# Video.net
KiCad netlist of a schematic drawn in Altium Designer
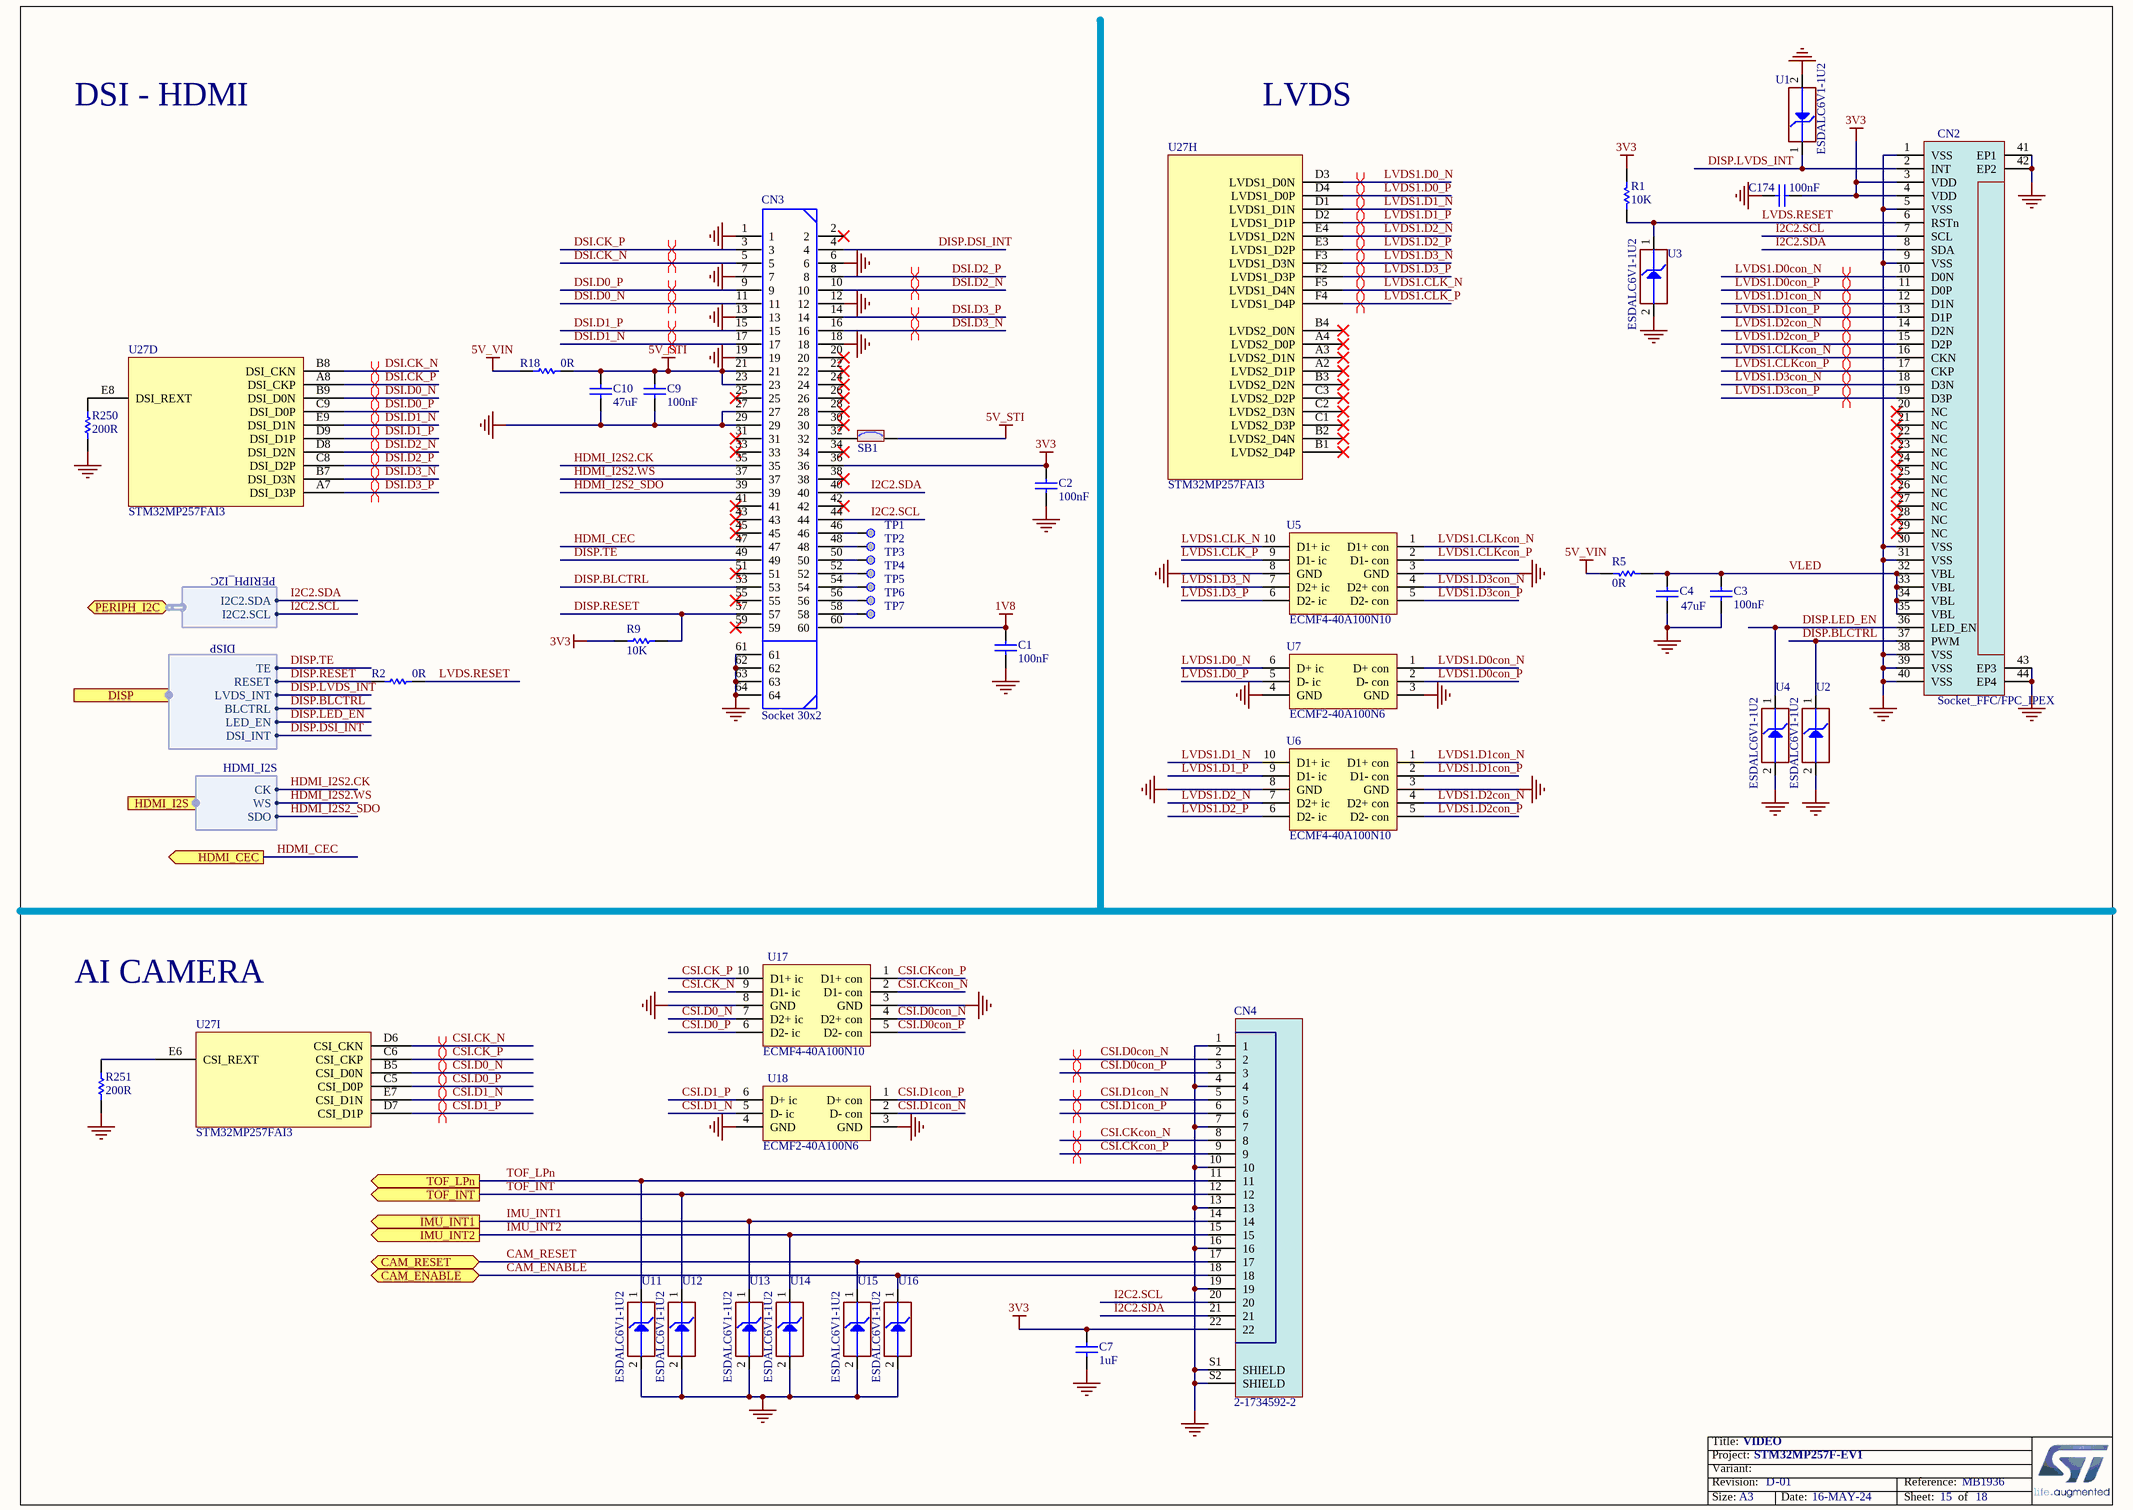
[diagram p0: Video.SchDoc]

(export (version "E")
  (design (tool "Eeschema 10.0.6"))
  (components
    (comp (ref "C1")
      (value "100nF")
      (footprint "MCD_PARTS:C0402")
      (description "Capacitor, MLCC, 100nF, 10V, X5R, +/-10%, 0402, T=0,5mm")
      (fields (field (name "INTERNAL_PART_NUMBER") "MCD-02352") (field (name "MANUFACTURER") "YAGEO"))
      (libsource (lib "MCD_PARTS_database") (part "Capacitor"))
    )
    (comp (ref "C2")
      (value "100nF")
      (footprint "MCD_PARTS:C0402")
      (description "Capacitor, MLCC, 100nF, 10V, X5R, +/-10%, 0402, T=0,5mm")
      (fields (field (name "INTERNAL_PART_NUMBER") "MCD-02352") (field (name "MANUFACTURER") "YAGEO"))
      (libsource (lib "MCD_PARTS_database") (part "Capacitor"))
    )
    (comp (ref "C3")
      (value "100nF")
      (footprint "MCD_PARTS:C0402")
      (description "Capacitor, MLCC, 100nF, 10V, X5R, +/-10%, 0402, T=0,5mm")
      (fields (field (name "INTERNAL_PART_NUMBER") "MCD-02352") (field (name "MANUFACTURER") "YAGEO"))
      (libsource (lib "MCD_PARTS_database") (part "Capacitor"))
    )
    (comp (ref "C4")
      (value "47uF")
      (footprint "MCD_PARTS:C0805")
      (description "Capacitor, MLCC, 47uF, 10V, X5R, +/-20%, 0805, T=1.25mm")
      (fields (field (name "INTERNAL_PART_NUMBER") "MCD-00204") (field (name "MANUFACTURER") "MURATA"))
      (libsource (lib "MCD_PARTS_database") (part "Capacitor"))
    )
    (comp (ref "C7")
      (value "1uF")
      (footprint "MCD_PARTS:C0402")
      (description "Capacitor, MLCC, 1uF, 25V, X5R, +/-10%, 0402, T=0,5mm")
      (fields
        (field (name "INTERNAL_PART_NUMBER") "MCD-00095")
        (field (name "MANUFACTURER_PART_NUMBER") "GRM155R61E105KA12")
      )
      (libsource (lib "MCD_PARTS_database") (part "Capacitor"))
    )
    (comp (ref "C9")
      (value "100nF")
      (footprint "MCD_PARTS:C0402")
      (description "Capacitor, MLCC, 100nF, 10V, X5R, +/-10%, 0402, T=0,5mm")
      (fields (field (name "INTERNAL_PART_NUMBER") "MCD-02352") (field (name "MANUFACTURER") "YAGEO"))
      (libsource (lib "MCD_PARTS_database") (part "Capacitor"))
    )
    (comp (ref "C10")
      (value "47uF")
      (footprint "MCD_PARTS:C0805")
      (description "Capacitor, MLCC, 47uF, 10V, X5R, +/-20%, 0805, T=1.25mm")
      (fields (field (name "INTERNAL_PART_NUMBER") "MCD-00204") (field (name "MANUFACTURER") "MURATA"))
      (libsource (lib "MCD_PARTS_database") (part "Capacitor"))
    )
    (comp (ref "C174")
      (value "100nF")
      (footprint "MCD_PARTS:C0402")
      (description "Capacitor, MLCC, 100nF, 10V, X5R, +/-10%, 0402, T=0,5mm")
      (fields (field (name "INTERNAL_PART_NUMBER") "MCD-02352") (field (name "MANUFACTURER") "YAGEO"))
      (libsource (lib "MCD_PARTS_database") (part "Capacitor"))
    )
    (comp (ref "CN2")
      (value "Socket_FFC/FPC_IPEX")
      (footprint "MCD_PARTS:CON_I-PEX_20455-040E-76")
      (description "Socket_FFC/FPC, 40pins, 0.5mm, RA, SMD, T=1mm")
      (fields (field (name "INTERNAL_PART_NUMBER") "MCD-03562") (field (name "MANUFACTURER") "I-PEX"))
      (libsource (lib "MCD_PARTS_database") (part "IPEX20455"))
    )
    (comp (ref "CN3")
      (value "Socket 30x2")
      (footprint "MCD_PARTS:CON_SAMTEC_QSH-030-01-F-D-A")
      (description "Socket, 30x2, 0.5mm, VR, SMD, T=3.05mm")
      (fields (field (name "INTERNAL_PART_NUMBER") "MCD-00137") (field (name "BMS_PART_NUMBER") "9183715"))
      (libsource (lib "MCD_PARTS_database") (part "Socket QSH-030-01-F-D-A"))
    )
    (comp (ref "CN4")
      (value "2-1734592-2")
      (footprint "MCD_PARTS:CON_TE-CONNECTIVITY_2-1734592-2_INV")
      (description "Socket_FFC/FPC, 22pins, 0.5mm, RA, SMD, T=2mm")
      (fields
        (field (name "INTERNAL_PART_NUMBER") "MCD-03600")
        (field (name "MANUFACTURER") "TE CONNECTIVITY")
      )
      (libsource (lib "MCD_PARTS_database") (part "2-1734592-2"))
    )
    (comp (ref "R1")
      (value "10K")
      (footprint "MCD_PARTS:R0402")
      (description "Resistor, 10K, 0402, +/-1%, 1/16W")
      (fields (field (name "INTERNAL_PART_NUMBER") "MCD-00053") (field (name "BMS_PART_NUMBER") "9131590"))
      (libsource (lib "MCD_PARTS_database") (part "Resistor"))
    )
    (comp (ref "R2")
      (value "0R")
      (footprint "MCD_PARTS:R0402")
      (description "Resistor, 0R, 0402, +/-5%, 1/16W")
      (fields (field (name "INTERNAL_PART_NUMBER") "MCD-00052") (field (name "MANUFACTURER") "YAGEO"))
      (libsource (lib "MCD_PARTS_database") (part "Resistor"))
    )
    (comp (ref "R5")
      (value "0R")
      (footprint "MCD_PARTS:R0805")
      (description "Resistor, 0R, 0805, +/-5%, 1/8W")
      (fields (field (name "INTERNAL_PART_NUMBER") "MCD-00179") (field (name "MANUFACTURER") "YAGEO"))
      (libsource (lib "MCD_PARTS_database") (part "Resistor"))
    )
    (comp (ref "R9")
      (value "10K")
      (footprint "MCD_PARTS:R0402")
      (description "Resistor, 10K, 0402, +/-1%, 1/16W")
      (fields (field (name "INTERNAL_PART_NUMBER") "MCD-00053") (field (name "BMS_PART_NUMBER") "9131590"))
      (libsource (lib "MCD_PARTS_database") (part "Resistor"))
    )
    (comp (ref "R18")
      (value "0R")
      (footprint "MCD_PARTS:R0402")
      (description "Resistor, 0R, 0402, +/-5%, 1/16W")
      (fields (field (name "INTERNAL_PART_NUMBER") "MCD-00052") (field (name "MANUFACTURER") "YAGEO"))
      (libsource (lib "MCD_PARTS_database") (part "Resistor"))
    )
    (comp (ref "R250")
      (value "200R")
      (footprint "MCD_PARTS:R0402")
      (description "Resistor, 200R, 0402, +/-1%, 1/16W")
      (fields
        (field (name "INTERNAL_PART_NUMBER") "MCD-00417")
        (field (name "MANUFACTURER_PART_NUMBER") "RC0402FR-07200RL")
      )
      (libsource (lib "MCD_PARTS_database") (part "Resistor"))
    )
    (comp (ref "R251")
      (value "200R")
      (footprint "MCD_PARTS:R0402")
      (description "Resistor, 200R, 0402, +/-1%, 1/16W")
      (fields
        (field (name "INTERNAL_PART_NUMBER") "MCD-00417")
        (field (name "MANUFACTURER_PART_NUMBER") "RC0402FR-07200RL")
      )
      (libsource (lib "MCD_PARTS_database") (part "Resistor"))
    )
    (comp (ref "SB1")
      (value "SB_ON")
      (footprint "MCD_PARTS:SOLDER-BRIDGE_R0603-0R")
      (description "Solder Bridge ON")
      (fields (field (name "INTERNAL_PART_NUMBER") "MCD-00071") (field (name "MANUFACTURER") "YAGEO"))
      (libsource (lib "MCD_PARTS_database") (part "SB_ON"))
    )
    (comp (ref "TP1")
      (value "Test Point")
      (footprint "MCD_PARTS:TP_SMD_1MM")
      (description "Test Point 1mm")
      (fields
        (field (name "INTERNAL_PART_NUMBER") "MCD-00074")
        (field (name "MANUFACTURER_PART_NUMBER") "n/a")
      )
      (libsource (lib "MCD_PARTS_database") (part "Test Point"))
    )
    (comp (ref "TP2")
      (value "Test Point")
      (footprint "MCD_PARTS:TP_SMD_1MM")
      (description "Test Point 1mm")
      (fields
        (field (name "INTERNAL_PART_NUMBER") "MCD-00074")
        (field (name "MANUFACTURER_PART_NUMBER") "n/a")
      )
      (libsource (lib "MCD_PARTS_database") (part "Test Point"))
    )
    (comp (ref "TP3")
      (value "Test Point")
      (footprint "MCD_PARTS:TP_SMD_1MM")
      (description "Test Point 1mm")
      (fields
        (field (name "INTERNAL_PART_NUMBER") "MCD-00074")
        (field (name "MANUFACTURER_PART_NUMBER") "n/a")
      )
      (libsource (lib "MCD_PARTS_database") (part "Test Point"))
    )
    (comp (ref "TP4")
      (value "Test Point")
      (footprint "MCD_PARTS:TP_SMD_1MM")
      (description "Test Point 1mm")
      (fields
        (field (name "INTERNAL_PART_NUMBER") "MCD-00074")
        (field (name "MANUFACTURER_PART_NUMBER") "n/a")
      )
      (libsource (lib "MCD_PARTS_database") (part "Test Point"))
    )
    (comp (ref "TP5")
      (value "Test Point")
      (footprint "MCD_PARTS:TP_SMD_1MM")
      (description "Test Point 1mm")
      (fields
        (field (name "INTERNAL_PART_NUMBER") "MCD-00074")
        (field (name "MANUFACTURER_PART_NUMBER") "n/a")
      )
      (libsource (lib "MCD_PARTS_database") (part "Test Point"))
    )
    (comp (ref "TP6")
      (value "Test Point")
      (footprint "MCD_PARTS:TP_SMD_1MM")
      (description "Test Point 1mm")
      (fields
        (field (name "INTERNAL_PART_NUMBER") "MCD-00074")
        (field (name "MANUFACTURER_PART_NUMBER") "n/a")
      )
      (libsource (lib "MCD_PARTS_database") (part "Test Point"))
    )
    (comp (ref "TP7")
      (value "Test Point")
      (footprint "MCD_PARTS:TP_SMD_1MM")
      (description "Test Point 1mm")
      (fields
        (field (name "INTERNAL_PART_NUMBER") "MCD-00074")
        (field (name "MANUFACTURER_PART_NUMBER") "n/a")
      )
      (libsource (lib "MCD_PARTS_database") (part "Test Point"))
    )
    (comp (ref "U1")
      (value "ESDALC6V1-1U2")
      (footprint "MCD_PARTS:ESD_ST0201")
      (description "ESD protection 6V1")
      (fields (field (name "INTERNAL_PART_NUMBER") "MCD-00170") (field (name "BMS_PART_NUMBER") "9151132"))
      (libsource (lib "") (part "ESD-TRANSIL_1"))
    )
    (comp (ref "U2")
      (value "ESDALC6V1-1U2")
      (footprint "MCD_PARTS:ESD_ST0201")
      (description "ESD protection 6V1")
      (fields (field (name "INTERNAL_PART_NUMBER") "MCD-00170") (field (name "BMS_PART_NUMBER") "9151132"))
      (libsource (lib "MCD_PARTS_database") (part "ESD-TRANSIL"))
    )
    (comp (ref "U3")
      (value "ESDALC6V1-1U2")
      (footprint "MCD_PARTS:ESD_ST0201")
      (description "ESD protection 6V1")
      (fields (field (name "INTERNAL_PART_NUMBER") "MCD-00170") (field (name "BMS_PART_NUMBER") "9151132"))
      (libsource (lib "MCD_PARTS_database") (part "ESD-TRANSIL"))
    )
    (comp (ref "U4")
      (value "ESDALC6V1-1U2")
      (footprint "MCD_PARTS:ESD_ST0201")
      (description "ESD protection 6V1")
      (fields (field (name "INTERNAL_PART_NUMBER") "MCD-00170") (field (name "BMS_PART_NUMBER") "9151132"))
      (libsource (lib "MCD_PARTS_database") (part "ESD-TRANSIL"))
    )
    (comp (ref "U5")
      (value "ECMF4-40A100N10")
      (footprint "MCD_PARTS:ESD_UQFN-10L_2P25X1P4_P040")
      (description "ESD protection & Common Filter High Speed serial Interfaces , 0.4 pitch")
      (fields
        (field (name "INTERNAL_PART_NUMBER") "MCD-03059")
        (field (name "MANUFACTURER") "STMICROELECTRONICS")
      )
      (libsource (lib "MCD_PARTS_database") (part "ECMF4-40A100N10"))
    )
    (comp (ref "U6")
      (value "ECMF4-40A100N10")
      (footprint "MCD_PARTS:ESD_UQFN-10L_2P25X1P4_P040")
      (description "ESD protection & Common Filter High Speed serial Interfaces , 0.4 pitch")
      (fields
        (field (name "INTERNAL_PART_NUMBER") "MCD-03059")
        (field (name "MANUFACTURER") "STMICROELECTRONICS")
      )
      (libsource (lib "MCD_PARTS_database") (part "ECMF4-40A100N10"))
    )
    (comp (ref "U7")
      (value "ECMF2-40A100N6")
      (footprint "MCD_PARTS:ESD_UQFN-6L_1P45X1P4_P040")
      (description "ESD protection & Common Filter High Speed serial Interfaces , 0.4 pitch")
      (fields
        (field (name "INTERNAL_PART_NUMBER") "MCD-03060")
        (field (name "MANUFACTURER") "STMICROELECTRONICS")
      )
      (libsource (lib "MCD_PARTS_database") (part "ECMF2-40A100N6"))
    )
    (comp (ref "U11")
      (value "ESDALC6V1-1U2")
      (footprint "MCD_PARTS:ESD_ST0201")
      (description "ESD protection 6V1")
      (fields (field (name "INTERNAL_PART_NUMBER") "MCD-00170") (field (name "BMS_PART_NUMBER") "9151132"))
      (libsource (lib "MCD_PARTS_database") (part "ESD-TRANSIL"))
    )
    (comp (ref "U12")
      (value "ESDALC6V1-1U2")
      (footprint "MCD_PARTS:ESD_ST0201")
      (description "ESD protection 6V1")
      (fields (field (name "INTERNAL_PART_NUMBER") "MCD-00170") (field (name "BMS_PART_NUMBER") "9151132"))
      (libsource (lib "MCD_PARTS_database") (part "ESD-TRANSIL"))
    )
    (comp (ref "U13")
      (value "ESDALC6V1-1U2")
      (footprint "MCD_PARTS:ESD_ST0201")
      (description "ESD protection 6V1")
      (fields (field (name "INTERNAL_PART_NUMBER") "MCD-00170") (field (name "BMS_PART_NUMBER") "9151132"))
      (libsource (lib "MCD_PARTS_database") (part "ESD-TRANSIL"))
    )
    (comp (ref "U14")
      (value "ESDALC6V1-1U2")
      (footprint "MCD_PARTS:ESD_ST0201")
      (description "ESD protection 6V1")
      (fields (field (name "INTERNAL_PART_NUMBER") "MCD-00170") (field (name "BMS_PART_NUMBER") "9151132"))
      (libsource (lib "MCD_PARTS_database") (part "ESD-TRANSIL"))
    )
    (comp (ref "U15")
      (value "ESDALC6V1-1U2")
      (footprint "MCD_PARTS:ESD_ST0201")
      (description "ESD protection 6V1")
      (fields (field (name "INTERNAL_PART_NUMBER") "MCD-00170") (field (name "BMS_PART_NUMBER") "9151132"))
      (libsource (lib "MCD_PARTS_database") (part "ESD-TRANSIL"))
    )
    (comp (ref "U16")
      (value "ESDALC6V1-1U2")
      (footprint "MCD_PARTS:ESD_ST0201")
      (description "ESD protection 6V1")
      (fields (field (name "INTERNAL_PART_NUMBER") "MCD-00170") (field (name "BMS_PART_NUMBER") "9151132"))
      (libsource (lib "MCD_PARTS_database") (part "ESD-TRANSIL"))
    )
    (comp (ref "U17")
      (value "ECMF4-40A100N10")
      (footprint "MCD_PARTS:ESD_UQFN-10L_2P25X1P4_P040")
      (description "ESD protection & Common Filter High Speed serial Interfaces , 0.4 pitch")
      (fields
        (field (name "INTERNAL_PART_NUMBER") "MCD-03059")
        (field (name "MANUFACTURER") "STMICROELECTRONICS")
      )
      (libsource (lib "MCD_PARTS_database") (part "ECMF4-40A100N10"))
    )
    (comp (ref "U18")
      (value "ECMF2-40A100N6")
      (footprint "MCD_PARTS:ESD_UQFN-6L_1P45X1P4_P040")
      (description "ESD protection & Common Filter High Speed serial Interfaces , 0.4 pitch")
      (fields
        (field (name "INTERNAL_PART_NUMBER") "MCD-03060")
        (field (name "MANUFACTURER") "STMICROELECTRONICS")
      )
      (libsource (lib "MCD_PARTS_database") (part "ECMF2-40A100N6"))
    )
    (comp (ref "U27")
      (value "STM32MP257FAI3")
      (footprint "ICC_LFBGA436_18X18_P080_H1P70_STM32MP257_CODE-B0D1")
      (description "MPU, ARM Cortex-A35 + M33 32-bit MPU, 808KB RAM, With Crypto")
      (fields
        (field (name "INTERNAL_PART_NUMBER") "MCD-02000")
        (field (name "MANUFACTURER") "STMICROELECTRONICS")
      )
      (libsource (lib "MCD_PARTS_database") (part "STM32MP257FAI3"))
    )
  )
  (nets
    (net (code "4") (name "/CAM_ENABLE") (class "Default")
      (node (ref "CN4") (pin "18") (pinfunction "18_18") (pintype "passive"))
      (node (ref "U16") (pin "1") (pinfunction "IO1_1") (pintype "passive"))
    )
    (net (code "5") (name "/CAM_RESET") (class "Default")
      (node (ref "CN4") (pin "17") (pinfunction "17_17") (pintype "passive"))
      (node (ref "U15") (pin "1") (pinfunction "IO1_1") (pintype "passive"))
    )
    (net (code "6") (name "/CSI.CK_N") (class "Default")
      (node (ref "U17") (pin "9") (pinfunction "D1-_ic_9") (pintype "passive"))
      (node (ref "U27") (pin "D6") (pinfunction "CSI_CKN_D6") (pintype "passive"))
    )
    (net (code "7") (name "/CSI.CK_P") (class "Default")
      (node (ref "U17") (pin "10") (pinfunction "D1+_ic_10") (pintype "passive"))
      (node (ref "U27") (pin "C6") (pinfunction "CSI_CKP_C6") (pintype "passive"))
    )
    (net (code "8") (name "/CSI.CKcon_N") (class "Default")
      (node (ref "CN4") (pin "8") (pinfunction "8_8") (pintype "passive"))
      (node (ref "U17") (pin "2") (pinfunction "D1-_con_2") (pintype "passive"))
    )
    (net (code "9") (name "/CSI.CKcon_P") (class "Default")
      (node (ref "CN4") (pin "9") (pinfunction "9_9") (pintype "passive"))
      (node (ref "U17") (pin "1") (pinfunction "D1+_con_1") (pintype "passive"))
    )
    (net (code "10") (name "/CSI.D0_N") (class "Default")
      (node (ref "U17") (pin "7") (pinfunction "D2+_ic_7") (pintype "passive"))
      (node (ref "U27") (pin "B5") (pinfunction "CSI_D0N_B5") (pintype "passive"))
    )
    (net (code "11") (name "/CSI.D0_P") (class "Default")
      (node (ref "U17") (pin "6") (pinfunction "D2-_ic_6") (pintype "passive"))
      (node (ref "U27") (pin "C5") (pinfunction "CSI_D0P_C5") (pintype "passive"))
    )
    (net (code "12") (name "/CSI.D0con_N") (class "Default")
      (node (ref "CN4") (pin "2") (pinfunction "2_2") (pintype "passive"))
      (node (ref "U17") (pin "4") (pinfunction "D2+_con_4") (pintype "passive"))
    )
    (net (code "13") (name "/CSI.D0con_P") (class "Default")
      (node (ref "CN4") (pin "3") (pinfunction "3_3") (pintype "passive"))
      (node (ref "U17") (pin "5") (pinfunction "D2-_con_5") (pintype "passive"))
    )
    (net (code "14") (name "/CSI.D1_N") (class "Default")
      (node (ref "U18") (pin "5") (pinfunction "D-_ic_5") (pintype "passive"))
      (node (ref "U27") (pin "E7") (pinfunction "CSI_D1N_E7") (pintype "passive"))
    )
    (net (code "15") (name "/CSI.D1_P") (class "Default")
      (node (ref "U18") (pin "6") (pinfunction "D+_ic_6") (pintype "passive"))
      (node (ref "U27") (pin "D7") (pinfunction "CSI_D1P_D7") (pintype "passive"))
    )
    (net (code "16") (name "/CSI.D1con_N") (class "Default")
      (node (ref "CN4") (pin "5") (pinfunction "5_5") (pintype "passive"))
      (node (ref "U18") (pin "2") (pinfunction "D-_con_2") (pintype "passive"))
    )
    (net (code "17") (name "/CSI.D1con_P") (class "Default")
      (node (ref "CN4") (pin "6") (pinfunction "6_6") (pintype "passive"))
      (node (ref "U18") (pin "1") (pinfunction "D+_con_1") (pintype "passive"))
    )
    (net (code "18") (name "/DISP.BLCTRL") (class "Default")
      (node (ref "CN2") (pin "37") (pinfunction "PWM_37") (pintype "passive"))
      (node (ref "CN3") (pin "53") (pinfunction "53_53") (pintype "passive"))
      (node (ref "U2") (pin "1") (pinfunction "IO1_1") (pintype "passive"))
    )
    (net (code "19") (name "/DISP.DSI_INT") (class "Default")
      (node (ref "CN3") (pin "4") (pinfunction "4_4") (pintype "passive"))
    )
    (net (code "20") (name "/DISP.LED_EN") (class "Default")
      (node (ref "CN2") (pin "36") (pinfunction "LED_EN_36") (pintype "passive"))
      (node (ref "U4") (pin "1") (pinfunction "IO1_1") (pintype "passive"))
    )
    (net (code "21") (name "/DISP.LVDS_INT") (class "Default")
      (node (ref "CN2") (pin "2") (pinfunction "INT_2") (pintype "passive"))
      (node (ref "U1") (pin "1") (pinfunction "IO1_1") (pintype "passive"))
    )
    (net (code "22") (name "/DISP.RESET") (class "Default")
      (node (ref "CN3") (pin "57") (pinfunction "57_57") (pintype "passive"))
      (node (ref "R2") (pin "1") (pinfunction "1_1") (pintype "passive"))
      (node (ref "R9") (pin "2") (pinfunction "2_2") (pintype "passive"))
    )
    (net (code "23") (name "/DISP.TE") (class "Default")
      (node (ref "CN3") (pin "49") (pinfunction "49_49") (pintype "passive"))
    )
    (net (code "24") (name "/DSI.CK_N") (class "Default")
      (node (ref "CN3") (pin "5") (pinfunction "5_5") (pintype "passive"))
      (node (ref "U27") (pin "B8") (pinfunction "DSI_CKN_B8") (pintype "passive"))
    )
    (net (code "25") (name "/DSI.CK_P") (class "Default")
      (node (ref "CN3") (pin "3") (pinfunction "3_3") (pintype "passive"))
      (node (ref "U27") (pin "A8") (pinfunction "DSI_CKP_A8") (pintype "passive"))
    )
    (net (code "26") (name "/DSI.D0_N") (class "Default")
      (node (ref "CN3") (pin "11") (pinfunction "11_11") (pintype "passive"))
      (node (ref "U27") (pin "B9") (pinfunction "DSI_D0N_B9") (pintype "passive"))
    )
    (net (code "27") (name "/DSI.D0_P") (class "Default")
      (node (ref "CN3") (pin "9") (pinfunction "9_9") (pintype "passive"))
      (node (ref "U27") (pin "C9") (pinfunction "DSI_D0P_C9") (pintype "passive"))
    )
    (net (code "28") (name "/DSI.D1_N") (class "Default")
      (node (ref "CN3") (pin "17") (pinfunction "17_17") (pintype "passive"))
      (node (ref "U27") (pin "E9") (pinfunction "DSI_D1N_E9") (pintype "passive"))
    )
    (net (code "29") (name "/DSI.D1_P") (class "Default")
      (node (ref "CN3") (pin "15") (pinfunction "15_15") (pintype "passive"))
      (node (ref "U27") (pin "D9") (pinfunction "DSI_D1P_D9") (pintype "passive"))
    )
    (net (code "30") (name "/DSI.D2_N") (class "Default")
      (node (ref "CN3") (pin "10") (pinfunction "10_10") (pintype "passive"))
      (node (ref "U27") (pin "D8") (pinfunction "DSI_D2N_D8") (pintype "passive"))
    )
    (net (code "31") (name "/DSI.D2_P") (class "Default")
      (node (ref "CN3") (pin "8") (pinfunction "8_8") (pintype "passive"))
      (node (ref "U27") (pin "C8") (pinfunction "DSI_D2P_C8") (pintype "passive"))
    )
    (net (code "32") (name "/DSI.D3_N") (class "Default")
      (node (ref "CN3") (pin "16") (pinfunction "16_16") (pintype "passive"))
      (node (ref "U27") (pin "B7") (pinfunction "DSI_D3N_B7") (pintype "passive"))
    )
    (net (code "33") (name "/DSI.D3_P") (class "Default")
      (node (ref "CN3") (pin "14") (pinfunction "14_14") (pintype "passive"))
      (node (ref "U27") (pin "A7") (pinfunction "DSI_D3P_A7") (pintype "passive"))
    )
    (net (code "34") (name "/HDMI_CEC") (class "Default")
      (node (ref "CN3") (pin "47") (pinfunction "47_47") (pintype "passive"))
    )
    (net (code "35") (name "/HDMI_I2S2.CK") (class "Default")
      (node (ref "CN3") (pin "35") (pinfunction "35_35") (pintype "passive"))
    )
    (net (code "36") (name "/HDMI_I2S2.WS") (class "Default")
      (node (ref "CN3") (pin "37") (pinfunction "37_37") (pintype "passive"))
    )
    (net (code "37") (name "/HDMI_I2S2_SDO") (class "Default")
      (node (ref "CN3") (pin "39") (pinfunction "39_39") (pintype "passive"))
    )
    (net (code "38") (name "/I2C2.SCL") (class "Default")
      (node (ref "CN2") (pin "7") (pinfunction "SCL_7") (pintype "passive"))
      (node (ref "CN3") (pin "44") (pinfunction "44_44") (pintype "passive"))
      (node (ref "CN4") (pin "20") (pinfunction "20_20") (pintype "passive"))
    )
    (net (code "39") (name "/I2C2.SDA") (class "Default")
      (node (ref "CN2") (pin "8") (pinfunction "SDA_8") (pintype "passive"))
      (node (ref "CN3") (pin "40") (pinfunction "40_40") (pintype "passive"))
      (node (ref "CN4") (pin "21") (pinfunction "21_21") (pintype "passive"))
    )
    (net (code "40") (name "/IMU_INT1") (class "Default")
      (node (ref "CN4") (pin "14") (pinfunction "14_14") (pintype "passive"))
      (node (ref "U13") (pin "1") (pinfunction "IO1_1") (pintype "passive"))
    )
    (net (code "41") (name "/IMU_INT2") (class "Default")
      (node (ref "CN4") (pin "15") (pinfunction "15_15") (pintype "passive"))
      (node (ref "U14") (pin "1") (pinfunction "IO1_1") (pintype "passive"))
    )
    (net (code "42") (name "/LVDS.RESET") (class "Default")
      (node (ref "CN2") (pin "6") (pinfunction "RSTn_6") (pintype "passive"))
      (node (ref "R1") (pin "2") (pinfunction "2_2") (pintype "passive"))
      (node (ref "R2") (pin "2") (pinfunction "2_2") (pintype "passive"))
      (node (ref "U3") (pin "1") (pinfunction "IO1_1") (pintype "passive"))
    )
    (net (code "43") (name "/LVDS1.CLK_N") (class "Default")
      (node (ref "U27") (pin "F5") (pinfunction "LVDS1_D4N_F5") (pintype "passive"))
      (node (ref "U5") (pin "10") (pinfunction "D1+_ic_10") (pintype "passive"))
    )
    (net (code "44") (name "/LVDS1.CLK_P") (class "Default")
      (node (ref "U27") (pin "F4") (pinfunction "LVDS1_D4P_F4") (pintype "passive"))
      (node (ref "U5") (pin "9") (pinfunction "D1-_ic_9") (pintype "passive"))
    )
    (net (code "45") (name "/LVDS1.CLKcon_N") (class "Default")
      (node (ref "CN2") (pin "16") (pinfunction "CKN_16") (pintype "passive"))
      (node (ref "U5") (pin "1") (pinfunction "D1+_con_1") (pintype "passive"))
    )
    (net (code "46") (name "/LVDS1.CLKcon_P") (class "Default")
      (node (ref "CN2") (pin "17") (pinfunction "CKP_17") (pintype "passive"))
      (node (ref "U5") (pin "2") (pinfunction "D1-_con_2") (pintype "passive"))
    )
    (net (code "47") (name "/LVDS1.D0_N") (class "Default")
      (node (ref "U27") (pin "D3") (pinfunction "LVDS1_D0N_D3") (pintype "passive"))
      (node (ref "U7") (pin "6") (pinfunction "D+_ic_6") (pintype "passive"))
    )
    (net (code "48") (name "/LVDS1.D0_P") (class "Default")
      (node (ref "U27") (pin "D4") (pinfunction "LVDS1_D0P_D4") (pintype "passive"))
      (node (ref "U7") (pin "5") (pinfunction "D-_ic_5") (pintype "passive"))
    )
    (net (code "49") (name "/LVDS1.D0con_N") (class "Default")
      (node (ref "CN2") (pin "10") (pinfunction "D0N_10") (pintype "passive"))
      (node (ref "U7") (pin "1") (pinfunction "D+_con_1") (pintype "passive"))
    )
    (net (code "50") (name "/LVDS1.D0con_P") (class "Default")
      (node (ref "CN2") (pin "11") (pinfunction "D0P_11") (pintype "passive"))
      (node (ref "U7") (pin "2") (pinfunction "D-_con_2") (pintype "passive"))
    )
    (net (code "51") (name "/LVDS1.D1_N") (class "Default")
      (node (ref "U27") (pin "D1") (pinfunction "LVDS1_D1N_D1") (pintype "passive"))
      (node (ref "U6") (pin "10") (pinfunction "D1+_ic_10") (pintype "passive"))
    )
    (net (code "52") (name "/LVDS1.D1_P") (class "Default")
      (node (ref "U27") (pin "D2") (pinfunction "LVDS1_D1P_D2") (pintype "passive"))
      (node (ref "U6") (pin "9") (pinfunction "D1-_ic_9") (pintype "passive"))
    )
    (net (code "53") (name "/LVDS1.D1con_N") (class "Default")
      (node (ref "CN2") (pin "12") (pinfunction "D1N_12") (pintype "passive"))
      (node (ref "U6") (pin "1") (pinfunction "D1+_con_1") (pintype "passive"))
    )
    (net (code "54") (name "/LVDS1.D1con_P") (class "Default")
      (node (ref "CN2") (pin "13") (pinfunction "D1P_13") (pintype "passive"))
      (node (ref "U6") (pin "2") (pinfunction "D1-_con_2") (pintype "passive"))
    )
    (net (code "55") (name "/LVDS1.D2_N") (class "Default")
      (node (ref "U27") (pin "E4") (pinfunction "LVDS1_D2N_E4") (pintype "passive"))
      (node (ref "U6") (pin "7") (pinfunction "D2+_ic_7") (pintype "passive"))
    )
    (net (code "56") (name "/LVDS1.D2_P") (class "Default")
      (node (ref "U27") (pin "E3") (pinfunction "LVDS1_D2P_E3") (pintype "passive"))
      (node (ref "U6") (pin "6") (pinfunction "D2-_ic_6") (pintype "passive"))
    )
    (net (code "57") (name "/LVDS1.D2con_N") (class "Default")
      (node (ref "CN2") (pin "14") (pinfunction "D2N_14") (pintype "passive"))
      (node (ref "U6") (pin "4") (pinfunction "D2+_con_4") (pintype "passive"))
    )
    (net (code "58") (name "/LVDS1.D2con_P") (class "Default")
      (node (ref "CN2") (pin "15") (pinfunction "D2P_15") (pintype "passive"))
      (node (ref "U6") (pin "5") (pinfunction "D2-_con_5") (pintype "passive"))
    )
    (net (code "59") (name "/LVDS1.D3_N") (class "Default")
      (node (ref "U27") (pin "F3") (pinfunction "LVDS1_D3N_F3") (pintype "passive"))
      (node (ref "U5") (pin "7") (pinfunction "D2+_ic_7") (pintype "passive"))
    )
    (net (code "60") (name "/LVDS1.D3_P") (class "Default")
      (node (ref "U27") (pin "F2") (pinfunction "LVDS1_D3P_F2") (pintype "passive"))
      (node (ref "U5") (pin "6") (pinfunction "D2-_ic_6") (pintype "passive"))
    )
    (net (code "61") (name "/LVDS1.D3con_N") (class "Default")
      (node (ref "CN2") (pin "18") (pinfunction "D3N_18") (pintype "passive"))
      (node (ref "U5") (pin "4") (pinfunction "D2+_con_4") (pintype "passive"))
    )
    (net (code "62") (name "/LVDS1.D3con_P") (class "Default")
      (node (ref "CN2") (pin "19") (pinfunction "D3P_19") (pintype "passive"))
      (node (ref "U5") (pin "5") (pinfunction "D2-_con_5") (pintype "passive"))
    )
    (net (code "63") (name "/TOF_INT") (class "Default")
      (node (ref "CN4") (pin "12") (pinfunction "12_12") (pintype "passive"))
      (node (ref "U12") (pin "1") (pinfunction "IO1_1") (pintype "passive"))
    )
    (net (code "64") (name "/TOF_LPn") (class "Default")
      (node (ref "CN4") (pin "11") (pinfunction "11_11") (pintype "passive"))
      (node (ref "U11") (pin "1") (pinfunction "IO1_1") (pintype "passive"))
    )
    (net (code "65") (name "/VLED") (class "Default")
      (node (ref "C3") (pin "2") (pinfunction "2_2") (pintype "passive"))
      (node (ref "C4") (pin "2") (pinfunction "2_2") (pintype "passive"))
      (node (ref "CN2") (pin "32") (pinfunction "VBL_32") (pintype "passive"))
      (node (ref "CN2") (pin "33") (pinfunction "VBL_33") (pintype "passive"))
      (node (ref "CN2") (pin "34") (pinfunction "VBL_34") (pintype "passive"))
      (node (ref "CN2") (pin "35") (pinfunction "VBL_35") (pintype "passive"))
      (node (ref "R5") (pin "1") (pinfunction "1_1") (pintype "passive"))
    )
    (net (code "69") (name "1V8") (class "Default")
      (node (ref "C1") (pin "2") (pinfunction "2_2") (pintype "passive"))
      (node (ref "CN3") (pin "60") (pinfunction "60_60") (pintype "passive"))
    )
    (net (code "70") (name "3V3") (class "Default")
      (node (ref "C174") (pin "2") (pinfunction "2_2") (pintype "passive"))
      (node (ref "C2") (pin "2") (pinfunction "2_2") (pintype "passive"))
      (node (ref "C7") (pin "2") (pinfunction "2_2") (pintype "passive"))
      (node (ref "CN2") (pin "3") (pinfunction "VDD_3") (pintype "passive"))
      (node (ref "CN2") (pin "4") (pinfunction "VDD_4") (pintype "passive"))
      (node (ref "CN3") (pin "36") (pinfunction "36_36") (pintype "passive"))
      (node (ref "CN4") (pin "22") (pinfunction "22_22") (pintype "passive"))
      (node (ref "R1") (pin "1") (pinfunction "1_1") (pintype "passive"))
      (node (ref "R9") (pin "1") (pinfunction "1_1") (pintype "passive"))
    )
    (net (code "71") (name "5V_STI") (class "Default")
      (node (ref "C10") (pin "2") (pinfunction "2_2") (pintype "passive"))
      (node (ref "C9") (pin "2") (pinfunction "2_2") (pintype "passive"))
      (node (ref "CN3") (pin "21") (pinfunction "21_21") (pintype "passive"))
      (node (ref "CN3") (pin "23") (pinfunction "23_23") (pintype "passive"))
      (node (ref "R18") (pin "2") (pinfunction "2_2") (pintype "passive"))
      (node (ref "SB1") (pin "2") (pinfunction "2_2") (pintype "passive"))
    )
    (net (code "72") (name "5V_VIN") (class "Default")
      (node (ref "R18") (pin "1") (pinfunction "1_1") (pintype "passive"))
      (node (ref "R5") (pin "2") (pinfunction "2_2") (pintype "passive"))
    )
    (net (code "73") (name "GND") (class "Default")
      (node (ref "C1") (pin "1") (pinfunction "1_1") (pintype "passive"))
      (node (ref "C10") (pin "1") (pinfunction "1_1") (pintype "passive"))
      (node (ref "C174") (pin "1") (pinfunction "1_1") (pintype "passive"))
      (node (ref "C2") (pin "1") (pinfunction "1_1") (pintype "passive"))
      (node (ref "C3") (pin "1") (pinfunction "1_1") (pintype "passive"))
      (node (ref "C4") (pin "1") (pinfunction "1_1") (pintype "passive"))
      (node (ref "C7") (pin "1") (pinfunction "1_1") (pintype "passive"))
      (node (ref "C9") (pin "1") (pinfunction "1_1") (pintype "passive"))
      (node (ref "CN2") (pin "1") (pinfunction "VSS_1") (pintype "passive"))
      (node (ref "CN2") (pin "30") (pinfunction "VSS_30") (pintype "passive"))
      (node (ref "CN2") (pin "31") (pinfunction "VSS_31") (pintype "passive"))
      (node (ref "CN2") (pin "38") (pinfunction "VSS_38") (pintype "passive"))
      (node (ref "CN2") (pin "39") (pinfunction "VSS_39") (pintype "passive"))
      (node (ref "CN2") (pin "40") (pinfunction "VSS_40") (pintype "passive"))
      (node (ref "CN2") (pin "41") (pinfunction "EP1_41") (pintype "passive"))
      (node (ref "CN2") (pin "42") (pinfunction "EP2_42") (pintype "passive"))
      (node (ref "CN2") (pin "43") (pinfunction "EP3_43") (pintype "passive"))
      (node (ref "CN2") (pin "44") (pinfunction "EP4_44") (pintype "passive"))
      (node (ref "CN2") (pin "5") (pinfunction "VSS_5") (pintype "passive"))
      (node (ref "CN2") (pin "9") (pinfunction "VSS_9") (pintype "passive"))
      (node (ref "CN3") (pin "1") (pinfunction "1_1") (pintype "passive"))
      (node (ref "CN3") (pin "12") (pinfunction "12_12") (pintype "passive"))
      (node (ref "CN3") (pin "13") (pinfunction "13_13") (pintype "passive"))
      (node (ref "CN3") (pin "18") (pinfunction "18_18") (pintype "passive"))
      (node (ref "CN3") (pin "19") (pinfunction "19_19") (pintype "passive"))
      (node (ref "CN3") (pin "27") (pinfunction "27_27") (pintype "passive"))
      (node (ref "CN3") (pin "29") (pinfunction "29_29") (pintype "passive"))
      (node (ref "CN3") (pin "6") (pinfunction "6_6") (pintype "passive"))
      (node (ref "CN3") (pin "61") (pinfunction "61_61") (pintype "passive"))
      (node (ref "CN3") (pin "62") (pinfunction "62_62") (pintype "passive"))
      (node (ref "CN3") (pin "63") (pinfunction "63_63") (pintype "passive"))
      (node (ref "CN3") (pin "64") (pinfunction "64_64") (pintype "passive"))
      (node (ref "CN3") (pin "7") (pinfunction "7_7") (pintype "passive"))
      (node (ref "CN4") (pin "1") (pinfunction "1_1") (pintype "passive"))
      (node (ref "CN4") (pin "10") (pinfunction "10_10") (pintype "passive"))
      (node (ref "CN4") (pin "13") (pinfunction "13_13") (pintype "passive"))
      (node (ref "CN4") (pin "16") (pinfunction "16_16") (pintype "passive"))
      (node (ref "CN4") (pin "19") (pinfunction "19_19") (pintype "passive"))
      (node (ref "CN4") (pin "4") (pinfunction "4_4") (pintype "passive"))
      (node (ref "CN4") (pin "7") (pinfunction "7_7") (pintype "passive"))
      (node (ref "CN4") (pin "S1") (pinfunction "SHIELD_S1") (pintype "passive"))
      (node (ref "CN4") (pin "S2") (pinfunction "SHIELD_S2") (pintype "passive"))
      (node (ref "R250") (pin "2") (pinfunction "2_2") (pintype "passive"))
      (node (ref "R251") (pin "2") (pinfunction "2_2") (pintype "passive"))
      (node (ref "U1") (pin "2") (pinfunction "GND_2") (pintype "passive"))
      (node (ref "U11") (pin "2") (pinfunction "GND_2") (pintype "passive"))
      (node (ref "U12") (pin "2") (pinfunction "GND_2") (pintype "passive"))
      (node (ref "U13") (pin "2") (pinfunction "GND_2") (pintype "passive"))
      (node (ref "U14") (pin "2") (pinfunction "GND_2") (pintype "passive"))
      (node (ref "U15") (pin "2") (pinfunction "GND_2") (pintype "passive"))
      (node (ref "U16") (pin "2") (pinfunction "GND_2") (pintype "passive"))
      (node (ref "U17") (pin "3") (pinfunction "GND_3") (pintype "passive"))
      (node (ref "U17") (pin "8") (pinfunction "GND_8") (pintype "passive"))
      (node (ref "U18") (pin "3") (pinfunction "GND_3") (pintype "passive"))
      (node (ref "U18") (pin "4") (pinfunction "GND_4") (pintype "passive"))
      (node (ref "U2") (pin "2") (pinfunction "GND_2") (pintype "passive"))
      (node (ref "U3") (pin "2") (pinfunction "GND_2") (pintype "passive"))
      (node (ref "U4") (pin "2") (pinfunction "GND_2") (pintype "passive"))
      (node (ref "U5") (pin "3") (pinfunction "GND_3") (pintype "passive"))
      (node (ref "U5") (pin "8") (pinfunction "GND_8") (pintype "passive"))
      (node (ref "U6") (pin "3") (pinfunction "GND_3") (pintype "passive"))
      (node (ref "U6") (pin "8") (pinfunction "GND_8") (pintype "passive"))
      (node (ref "U7") (pin "3") (pinfunction "GND_3") (pintype "passive"))
      (node (ref "U7") (pin "4") (pinfunction "GND_4") (pintype "passive"))
    )
    (net (code "74") (name "Net-(CN3-Pad32)") (class "Default")
      (node (ref "CN3") (pin "32") (pinfunction "32_32") (pintype "passive"))
      (node (ref "SB1") (pin "1") (pinfunction "1_1") (pintype "passive"))
    )
    (net (code "75") (name "Net-(CN3-Pad46)") (class "Default")
      (node (ref "CN3") (pin "46") (pinfunction "46_46") (pintype "passive"))
      (node (ref "TP1") (pin "1") (pinfunction "1_1") (pintype "passive"))
    )
    (net (code "76") (name "Net-(CN3-Pad48)") (class "Default")
      (node (ref "CN3") (pin "48") (pinfunction "48_48") (pintype "passive"))
      (node (ref "TP2") (pin "1") (pinfunction "1_1") (pintype "passive"))
    )
    (net (code "77") (name "Net-(CN3-Pad50)") (class "Default")
      (node (ref "CN3") (pin "50") (pinfunction "50_50") (pintype "passive"))
      (node (ref "TP3") (pin "1") (pinfunction "1_1") (pintype "passive"))
    )
    (net (code "78") (name "Net-(CN3-Pad52)") (class "Default")
      (node (ref "CN3") (pin "52") (pinfunction "52_52") (pintype "passive"))
      (node (ref "TP4") (pin "1") (pinfunction "1_1") (pintype "passive"))
    )
    (net (code "79") (name "Net-(CN3-Pad54)") (class "Default")
      (node (ref "CN3") (pin "54") (pinfunction "54_54") (pintype "passive"))
      (node (ref "TP5") (pin "1") (pinfunction "1_1") (pintype "passive"))
    )
    (net (code "80") (name "Net-(CN3-Pad56)") (class "Default")
      (node (ref "CN3") (pin "56") (pinfunction "56_56") (pintype "passive"))
      (node (ref "TP6") (pin "1") (pinfunction "1_1") (pintype "passive"))
    )
    (net (code "81") (name "Net-(CN3-Pad58)") (class "Default")
      (node (ref "CN3") (pin "58") (pinfunction "58_58") (pintype "passive"))
      (node (ref "TP7") (pin "1") (pinfunction "1_1") (pintype "passive"))
    )
    (net (code "82") (name "Net-(U27D-DSI_REXT)") (class "Default")
      (node (ref "R250") (pin "1") (pinfunction "1_1") (pintype "passive"))
      (node (ref "U27") (pin "E8") (pinfunction "DSI_REXT_E8") (pintype "passive"))
    )
    (net (code "83") (name "Net-(U27I-CSI_REXT)") (class "Default")
      (node (ref "R251") (pin "1") (pinfunction "1_1") (pintype "passive"))
      (node (ref "U27") (pin "E6") (pinfunction "CSI_REXT_E6") (pintype "passive"))
    )
    (net (code "84") (name "unconnected-(CN2-NC-Pad20)") (class "Default")
      (node (ref "CN2") (pin "20") (pinfunction "NC_20") (pintype "passive+no_connect"))
    )
    (net (code "85") (name "unconnected-(CN2-NC-Pad21)") (class "Default")
      (node (ref "CN2") (pin "21") (pinfunction "NC_21") (pintype "passive+no_connect"))
    )
    (net (code "86") (name "unconnected-(CN2-NC-Pad22)") (class "Default")
      (node (ref "CN2") (pin "22") (pinfunction "NC_22") (pintype "passive+no_connect"))
    )
    (net (code "87") (name "unconnected-(CN2-NC-Pad23)") (class "Default")
      (node (ref "CN2") (pin "23") (pinfunction "NC_23") (pintype "passive+no_connect"))
    )
    (net (code "88") (name "unconnected-(CN2-NC-Pad24)") (class "Default")
      (node (ref "CN2") (pin "24") (pinfunction "NC_24") (pintype "passive+no_connect"))
    )
    (net (code "89") (name "unconnected-(CN2-NC-Pad25)") (class "Default")
      (node (ref "CN2") (pin "25") (pinfunction "NC_25") (pintype "passive+no_connect"))
    )
    (net (code "90") (name "unconnected-(CN2-NC-Pad26)") (class "Default")
      (node (ref "CN2") (pin "26") (pinfunction "NC_26") (pintype "passive+no_connect"))
    )
    (net (code "91") (name "unconnected-(CN2-NC-Pad27)") (class "Default")
      (node (ref "CN2") (pin "27") (pinfunction "NC_27") (pintype "passive+no_connect"))
    )
    (net (code "92") (name "unconnected-(CN2-NC-Pad28)") (class "Default")
      (node (ref "CN2") (pin "28") (pinfunction "NC_28") (pintype "passive+no_connect"))
    )
    (net (code "93") (name "unconnected-(CN2-NC-Pad29)") (class "Default")
      (node (ref "CN2") (pin "29") (pinfunction "NC_29") (pintype "passive+no_connect"))
    )
    (net (code "94") (name "unconnected-(CN3-Pad2)") (class "Default")
      (node (ref "CN3") (pin "2") (pinfunction "2_2") (pintype "passive+no_connect"))
    )
    (net (code "95") (name "unconnected-(CN3-Pad20)") (class "Default")
      (node (ref "CN3") (pin "20") (pinfunction "20_20") (pintype "passive+no_connect"))
    )
    (net (code "96") (name "unconnected-(CN3-Pad22)") (class "Default")
      (node (ref "CN3") (pin "22") (pinfunction "22_22") (pintype "passive+no_connect"))
    )
    (net (code "97") (name "unconnected-(CN3-Pad24)") (class "Default")
      (node (ref "CN3") (pin "24") (pinfunction "24_24") (pintype "passive+no_connect"))
    )
    (net (code "98") (name "unconnected-(CN3-Pad25)") (class "Default")
      (node (ref "CN3") (pin "25") (pinfunction "25_25") (pintype "passive+no_connect"))
    )
    (net (code "99") (name "unconnected-(CN3-Pad26)") (class "Default")
      (node (ref "CN3") (pin "26") (pinfunction "26_26") (pintype "passive+no_connect"))
    )
    (net (code "100") (name "unconnected-(CN3-Pad28)") (class "Default")
      (node (ref "CN3") (pin "28") (pinfunction "28_28") (pintype "passive+no_connect"))
    )
    (net (code "101") (name "unconnected-(CN3-Pad30)") (class "Default")
      (node (ref "CN3") (pin "30") (pinfunction "30_30") (pintype "passive+no_connect"))
    )
    (net (code "102") (name "unconnected-(CN3-Pad31)") (class "Default")
      (node (ref "CN3") (pin "31") (pinfunction "31_31") (pintype "passive+no_connect"))
    )
    (net (code "103") (name "unconnected-(CN3-Pad33)") (class "Default")
      (node (ref "CN3") (pin "33") (pinfunction "33_33") (pintype "passive+no_connect"))
    )
    (net (code "104") (name "unconnected-(CN3-Pad34)") (class "Default")
      (node (ref "CN3") (pin "34") (pinfunction "34_34") (pintype "passive+no_connect"))
    )
    (net (code "105") (name "unconnected-(CN3-Pad38)") (class "Default")
      (node (ref "CN3") (pin "38") (pinfunction "38_38") (pintype "passive+no_connect"))
    )
    (net (code "106") (name "unconnected-(CN3-Pad41)") (class "Default")
      (node (ref "CN3") (pin "41") (pinfunction "41_41") (pintype "passive+no_connect"))
    )
    (net (code "107") (name "unconnected-(CN3-Pad42)") (class "Default")
      (node (ref "CN3") (pin "42") (pinfunction "42_42") (pintype "passive+no_connect"))
    )
    (net (code "108") (name "unconnected-(CN3-Pad43)") (class "Default")
      (node (ref "CN3") (pin "43") (pinfunction "43_43") (pintype "passive+no_connect"))
    )
    (net (code "109") (name "unconnected-(CN3-Pad45)") (class "Default")
      (node (ref "CN3") (pin "45") (pinfunction "45_45") (pintype "passive+no_connect"))
    )
    (net (code "110") (name "unconnected-(CN3-Pad51)") (class "Default")
      (node (ref "CN3") (pin "51") (pinfunction "51_51") (pintype "passive+no_connect"))
    )
    (net (code "111") (name "unconnected-(CN3-Pad55)") (class "Default")
      (node (ref "CN3") (pin "55") (pinfunction "55_55") (pintype "passive+no_connect"))
    )
    (net (code "112") (name "unconnected-(CN3-Pad59)") (class "Default")
      (node (ref "CN3") (pin "59") (pinfunction "59_59") (pintype "passive+no_connect"))
    )
    (net (code "113") (name "unconnected-(U27H-LVDS2_D0N-PadB4)") (class "Default")
      (node (ref "U27") (pin "B4") (pinfunction "LVDS2_D0N_B4") (pintype "passive+no_connect"))
    )
    (net (code "114") (name "unconnected-(U27H-LVDS2_D0P-PadA4)") (class "Default")
      (node (ref "U27") (pin "A4") (pinfunction "LVDS2_D0P_A4") (pintype "passive+no_connect"))
    )
    (net (code "115") (name "unconnected-(U27H-LVDS2_D1N-PadA3)") (class "Default")
      (node (ref "U27") (pin "A3") (pinfunction "LVDS2_D1N_A3") (pintype "passive+no_connect"))
    )
    (net (code "116") (name "unconnected-(U27H-LVDS2_D1P-PadA2)") (class "Default")
      (node (ref "U27") (pin "A2") (pinfunction "LVDS2_D1P_A2") (pintype "passive+no_connect"))
    )
    (net (code "117") (name "unconnected-(U27H-LVDS2_D2N-PadB3)") (class "Default")
      (node (ref "U27") (pin "B3") (pinfunction "LVDS2_D2N_B3") (pintype "passive+no_connect"))
    )
    (net (code "118") (name "unconnected-(U27H-LVDS2_D2P-PadC3)") (class "Default")
      (node (ref "U27") (pin "C3") (pinfunction "LVDS2_D2P_C3") (pintype "passive+no_connect"))
    )
    (net (code "119") (name "unconnected-(U27H-LVDS2_D3N-PadC2)") (class "Default")
      (node (ref "U27") (pin "C2") (pinfunction "LVDS2_D3N_C2") (pintype "passive+no_connect"))
    )
    (net (code "120") (name "unconnected-(U27H-LVDS2_D3P-PadC1)") (class "Default")
      (node (ref "U27") (pin "C1") (pinfunction "LVDS2_D3P_C1") (pintype "passive+no_connect"))
    )
    (net (code "121") (name "unconnected-(U27H-LVDS2_D4N-PadB2)") (class "Default")
      (node (ref "U27") (pin "B2") (pinfunction "LVDS2_D4N_B2") (pintype "passive+no_connect"))
    )
    (net (code "122") (name "unconnected-(U27H-LVDS2_D4P-PadB1)") (class "Default")
      (node (ref "U27") (pin "B1") (pinfunction "LVDS2_D4P_B1") (pintype "passive+no_connect"))
    )
  )
)
